# z80test.net
KiCad netlist of a schematic drawn in EAGLE
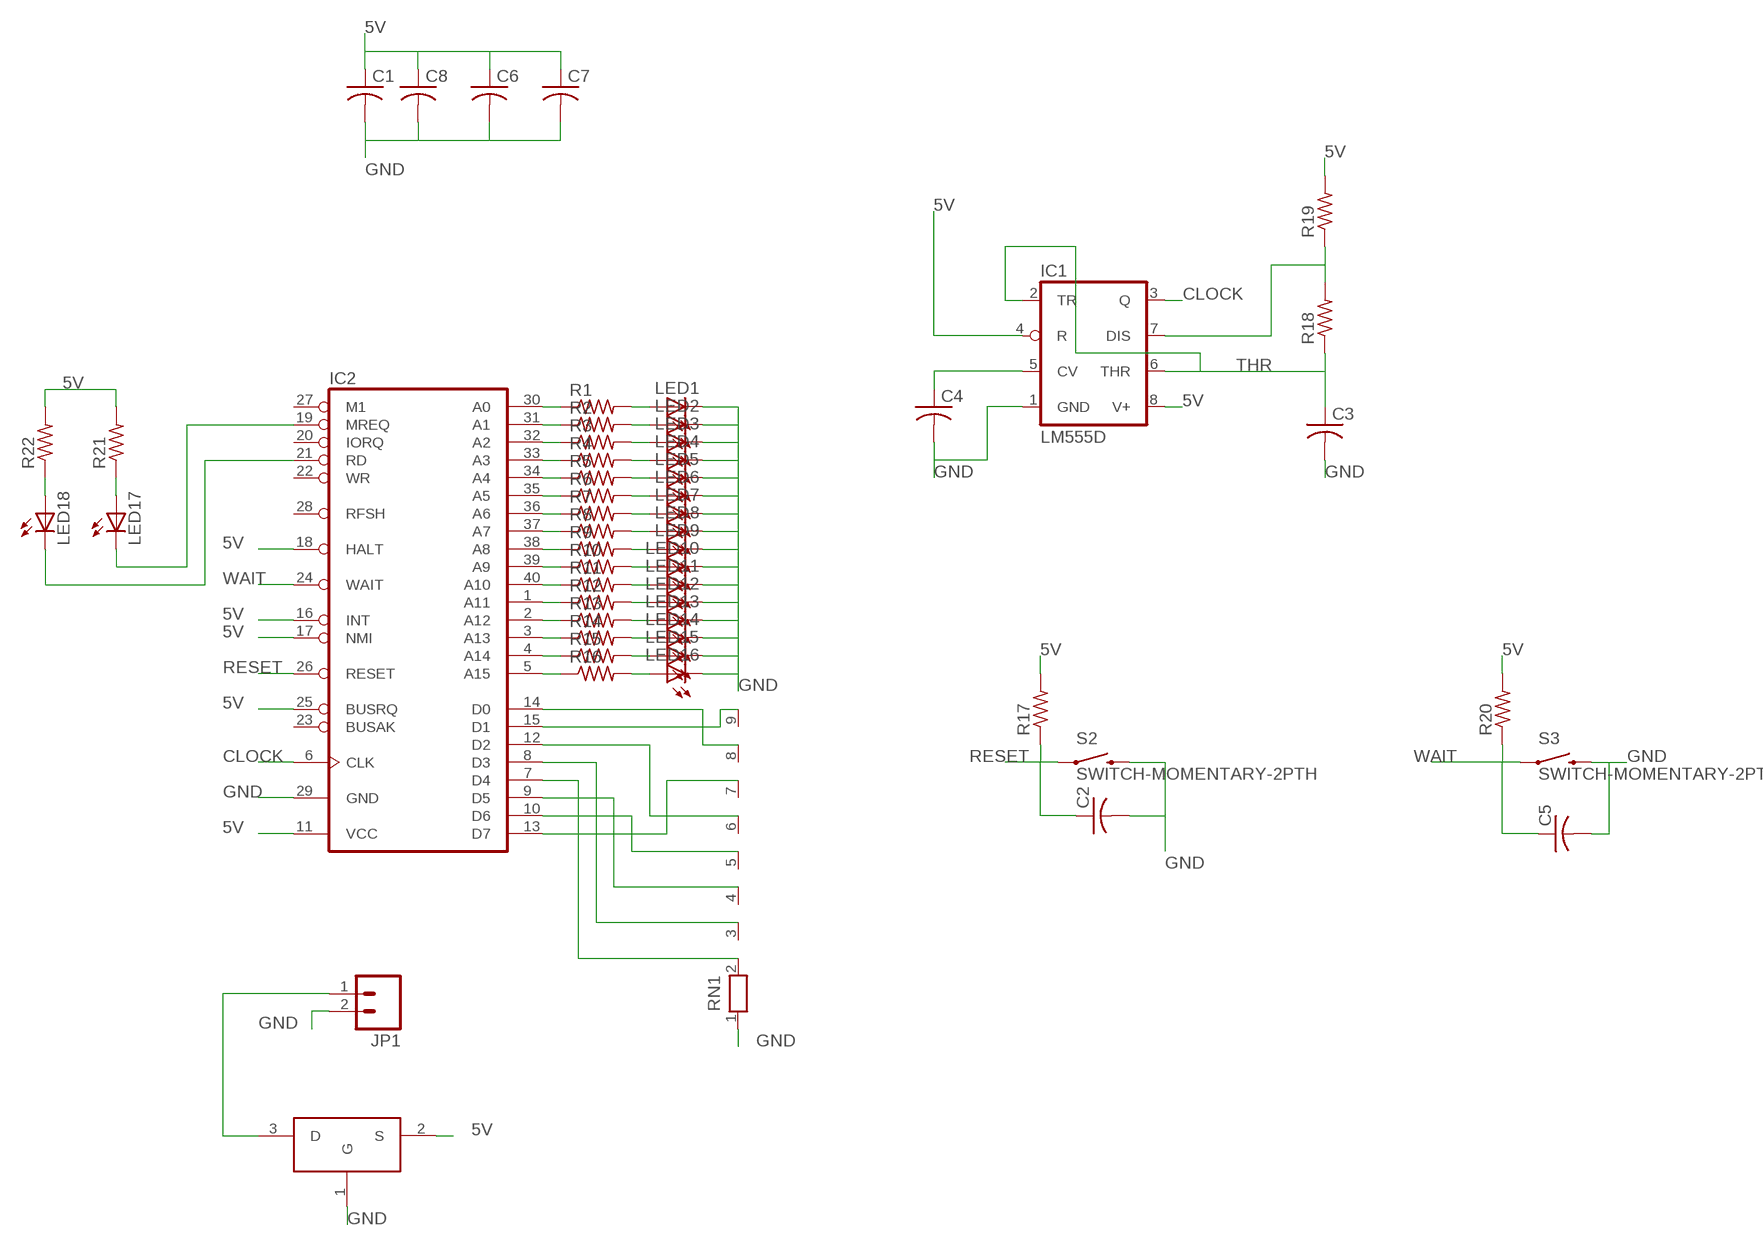
[diagram p0: schematic, sheet 1]

(export (version "E")
  (design (tool "Eeschema 10.0.6"))
  (components
    (comp (ref "C1")
      (value "C-USC0805K")
      (footprint "eagle-import:C0805K")
      (libsource (lib "eagle-import") (part "C-USC0805K"))
    )
    (comp (ref "C2")
      (value "C-USC0603")
      (footprint "eagle-import:C0603")
      (libsource (lib "eagle-import") (part "C-USC0603"))
    )
    (comp (ref "C3")
      (value "C-USC0603")
      (footprint "eagle-import:C0603")
      (libsource (lib "eagle-import") (part "C-USC0603"))
    )
    (comp (ref "C4")
      (value "C-USC0603")
      (footprint "eagle-import:C0603")
      (libsource (lib "eagle-import") (part "C-USC0603"))
    )
    (comp (ref "C5")
      (value "C-USC0603")
      (footprint "eagle-import:C0603")
      (libsource (lib "eagle-import") (part "C-USC0603"))
    )
    (comp (ref "C6")
      (value "C-USC0603")
      (footprint "eagle-import:C0603")
      (libsource (lib "eagle-import") (part "C-USC0603"))
    )
    (comp (ref "C7")
      (value "C-USC0603")
      (footprint "eagle-import:C0603")
      (libsource (lib "eagle-import") (part "C-USC0603"))
    )
    (comp (ref "C8")
      (value "C-USC0603")
      (footprint "eagle-import:C0603")
      (libsource (lib "eagle-import") (part "C-USC0603"))
    )
    (comp (ref "IC1")
      (value "LM555D")
      (footprint "eagle-import:SO08")
      (libsource (lib "eagle-import") (part "555DLM"))
    )
    (comp (ref "IC2")
      (value "Z80CPU")
      (footprint "eagle-import:DIL40")
      (libsource (lib "eagle-import") (part "Z80CPU"))
    )
    (comp (ref "JP1")
      (value "M02PTH")
      (footprint "eagle-import:1X02")
      (libsource (lib "eagle-import") (part "M02PTH"))
    )
    (comp (ref "LED1")
      (value "LEDCHIPLED_0805")
      (footprint "eagle-import:CHIPLED_0805")
      (libsource (lib "eagle-import") (part "LEDCHIPLED_0805"))
    )
    (comp (ref "LED2")
      (value "LEDCHIPLED_0805")
      (footprint "eagle-import:CHIPLED_0805")
      (libsource (lib "eagle-import") (part "LEDCHIPLED_0805"))
    )
    (comp (ref "LED3")
      (value "LEDCHIPLED_0805")
      (footprint "eagle-import:CHIPLED_0805")
      (libsource (lib "eagle-import") (part "LEDCHIPLED_0805"))
    )
    (comp (ref "LED4")
      (value "LEDCHIPLED_0805")
      (footprint "eagle-import:CHIPLED_0805")
      (libsource (lib "eagle-import") (part "LEDCHIPLED_0805"))
    )
    (comp (ref "LED5")
      (value "LEDCHIPLED_0805")
      (footprint "eagle-import:CHIPLED_0805")
      (libsource (lib "eagle-import") (part "LEDCHIPLED_0805"))
    )
    (comp (ref "LED6")
      (value "LEDCHIPLED_0805")
      (footprint "eagle-import:CHIPLED_0805")
      (libsource (lib "eagle-import") (part "LEDCHIPLED_0805"))
    )
    (comp (ref "LED7")
      (value "LEDCHIPLED_0805")
      (footprint "eagle-import:CHIPLED_0805")
      (libsource (lib "eagle-import") (part "LEDCHIPLED_0805"))
    )
    (comp (ref "LED8")
      (value "LEDCHIPLED_0805")
      (footprint "eagle-import:CHIPLED_0805")
      (libsource (lib "eagle-import") (part "LEDCHIPLED_0805"))
    )
    (comp (ref "LED9")
      (value "LEDCHIPLED_0805")
      (footprint "eagle-import:CHIPLED_0805")
      (libsource (lib "eagle-import") (part "LEDCHIPLED_0805"))
    )
    (comp (ref "LED10")
      (value "LEDCHIPLED_0805")
      (footprint "eagle-import:CHIPLED_0805")
      (libsource (lib "eagle-import") (part "LEDCHIPLED_0805"))
    )
    (comp (ref "LED11")
      (value "LEDCHIPLED_0805")
      (footprint "eagle-import:CHIPLED_0805")
      (libsource (lib "eagle-import") (part "LEDCHIPLED_0805"))
    )
    (comp (ref "LED12")
      (value "LEDCHIPLED_0805")
      (footprint "eagle-import:CHIPLED_0805")
      (libsource (lib "eagle-import") (part "LEDCHIPLED_0805"))
    )
    (comp (ref "LED13")
      (value "LEDCHIPLED_0805")
      (footprint "eagle-import:CHIPLED_0805")
      (libsource (lib "eagle-import") (part "LEDCHIPLED_0805"))
    )
    (comp (ref "LED14")
      (value "LEDCHIPLED_0805")
      (footprint "eagle-import:CHIPLED_0805")
      (libsource (lib "eagle-import") (part "LEDCHIPLED_0805"))
    )
    (comp (ref "LED15")
      (value "LEDCHIPLED_0805")
      (footprint "eagle-import:CHIPLED_0805")
      (libsource (lib "eagle-import") (part "LEDCHIPLED_0805"))
    )
    (comp (ref "LED16")
      (value "LEDCHIPLED_0805")
      (footprint "eagle-import:CHIPLED_0805")
      (libsource (lib "eagle-import") (part "LEDCHIPLED_0805"))
    )
    (comp (ref "LED17")
      (value "LEDCHIPLED_0805")
      (footprint "eagle-import:CHIPLED_0805")
      (libsource (lib "eagle-import") (part "LEDCHIPLED_0805"))
    )
    (comp (ref "LED18")
      (value "LEDCHIPLED_0805")
      (footprint "eagle-import:CHIPLED_0805")
      (libsource (lib "eagle-import") (part "LEDCHIPLED_0805"))
    )
    (comp (ref "R1")
      (value "R-US_R0603")
      (footprint "eagle-import:R0603")
      (libsource (lib "eagle-import") (part "R-US_R0603"))
    )
    (comp (ref "R2")
      (value "R-US_R0603")
      (footprint "eagle-import:R0603")
      (libsource (lib "eagle-import") (part "R-US_R0603"))
    )
    (comp (ref "R3")
      (value "R-US_R0603")
      (footprint "eagle-import:R0603")
      (libsource (lib "eagle-import") (part "R-US_R0603"))
    )
    (comp (ref "R4")
      (value "R-US_R0603")
      (footprint "eagle-import:R0603")
      (libsource (lib "eagle-import") (part "R-US_R0603"))
    )
    (comp (ref "R5")
      (value "R-US_R0603")
      (footprint "eagle-import:R0603")
      (libsource (lib "eagle-import") (part "R-US_R0603"))
    )
    (comp (ref "R6")
      (value "R-US_R0603")
      (footprint "eagle-import:R0603")
      (libsource (lib "eagle-import") (part "R-US_R0603"))
    )
    (comp (ref "R7")
      (value "R-US_R0603")
      (footprint "eagle-import:R0603")
      (libsource (lib "eagle-import") (part "R-US_R0603"))
    )
    (comp (ref "R8")
      (value "R-US_R0603")
      (footprint "eagle-import:R0603")
      (libsource (lib "eagle-import") (part "R-US_R0603"))
    )
    (comp (ref "R9")
      (value "R-US_R0603")
      (footprint "eagle-import:R0603")
      (libsource (lib "eagle-import") (part "R-US_R0603"))
    )
    (comp (ref "R10")
      (value "R-US_R0603")
      (footprint "eagle-import:R0603")
      (libsource (lib "eagle-import") (part "R-US_R0603"))
    )
    (comp (ref "R11")
      (value "R-US_R0603")
      (footprint "eagle-import:R0603")
      (libsource (lib "eagle-import") (part "R-US_R0603"))
    )
    (comp (ref "R12")
      (value "R-US_R0603")
      (footprint "eagle-import:R0603")
      (libsource (lib "eagle-import") (part "R-US_R0603"))
    )
    (comp (ref "R13")
      (value "R-US_R0603")
      (footprint "eagle-import:R0603")
      (libsource (lib "eagle-import") (part "R-US_R0603"))
    )
    (comp (ref "R14")
      (value "R-US_R0603")
      (footprint "eagle-import:R0603")
      (libsource (lib "eagle-import") (part "R-US_R0603"))
    )
    (comp (ref "R15")
      (value "R-US_R0603")
      (footprint "eagle-import:R0603")
      (libsource (lib "eagle-import") (part "R-US_R0603"))
    )
    (comp (ref "R16")
      (value "R-US_R0603")
      (footprint "eagle-import:R0603")
      (libsource (lib "eagle-import") (part "R-US_R0603"))
    )
    (comp (ref "R17")
      (value "R-US_R0603")
      (footprint "eagle-import:R0603")
      (libsource (lib "eagle-import") (part "R-US_R0603"))
    )
    (comp (ref "R18")
      (value "R-US_R0603")
      (footprint "eagle-import:R0603")
      (libsource (lib "eagle-import") (part "R-US_R0603"))
    )
    (comp (ref "R19")
      (value "R-US_R0603")
      (footprint "eagle-import:R0603")
      (libsource (lib "eagle-import") (part "R-US_R0603"))
    )
    (comp (ref "R20")
      (value "R-US_R0603")
      (footprint "eagle-import:R0603")
      (libsource (lib "eagle-import") (part "R-US_R0603"))
    )
    (comp (ref "R21")
      (value "R-US_R0603")
      (footprint "eagle-import:R0603")
      (libsource (lib "eagle-import") (part "R-US_R0603"))
    )
    (comp (ref "R22")
      (value "R-US_R0603")
      (footprint "eagle-import:R0603")
      (libsource (lib "eagle-import") (part "R-US_R0603"))
    )
    (comp (ref "RN1")
      (value "RN08")
      (footprint "eagle-import:RN-9")
      (libsource (lib "eagle-import") (part "RN08"))
    )
    (comp (ref "S2")
      (value "SWITCH-MOMENTARY-2PTH")
      (footprint "eagle-import:TACTILE-PTH")
      (libsource (lib "eagle-import") (part "SWITCH-MOMENTARY-2PTH"))
    )
    (comp (ref "S3")
      (value "SWITCH-MOMENTARY-2PTH")
      (footprint "eagle-import:TACTILE-PTH")
      (libsource (lib "eagle-import") (part "SWITCH-MOMENTARY-2PTH"))
    )
    (comp (ref "U$1")
      (value "PMOS_RP")
      (footprint "eagle-import:SOT23-3")
      (libsource (lib "eagle-import") (part "PMOS_RP"))
    )
  )
  (nets
    (net (code "1") (name "/5V") (class "Default")
      (node (ref "C1") (pin "1") (pinfunction "1_1") (pintype "passive"))
      (node (ref "C6") (pin "1") (pinfunction "1_1") (pintype "passive"))
      (node (ref "C7") (pin "1") (pinfunction "1_1") (pintype "passive"))
      (node (ref "C8") (pin "1") (pinfunction "1_1") (pintype "passive"))
      (node (ref "IC1") (pin "4") (pinfunction "R_4") (pintype "input"))
      (node (ref "IC1") (pin "8") (pinfunction "V+_8") (pintype "power_in"))
      (node (ref "IC2") (pin "11") (pinfunction "VCC_11") (pintype "power_in"))
      (node (ref "IC2") (pin "16") (pinfunction "INT_16") (pintype "input"))
      (node (ref "IC2") (pin "17") (pinfunction "NMI_17") (pintype "input"))
      (node (ref "IC2") (pin "18") (pinfunction "HALT_18") (pintype "output"))
      (node (ref "IC2") (pin "25") (pinfunction "BUSRQ_25") (pintype "input"))
      (node (ref "R17") (pin "2") (pinfunction "2_2") (pintype "passive"))
      (node (ref "R19") (pin "2") (pinfunction "2_2") (pintype "passive"))
      (node (ref "R20") (pin "2") (pinfunction "2_2") (pintype "passive"))
      (node (ref "R21") (pin "2") (pinfunction "2_2") (pintype "passive"))
      (node (ref "R22") (pin "2") (pinfunction "2_2") (pintype "passive"))
      (node (ref "U$1") (pin "2") (pinfunction "S_2") (pintype "bidirectional"))
    )
    (net (code "2") (name "/CLOCK") (class "Default")
      (node (ref "IC1") (pin "3") (pinfunction "Q_3") (pintype "output"))
      (node (ref "IC2") (pin "6") (pinfunction "CLK_6") (pintype "input"))
    )
    (net (code "3") (name "/GND") (class "Default")
      (node (ref "C1") (pin "2") (pinfunction "2_2") (pintype "passive"))
      (node (ref "C2") (pin "2") (pinfunction "2_2") (pintype "passive"))
      (node (ref "C3") (pin "2") (pinfunction "2_2") (pintype "passive"))
      (node (ref "C4") (pin "2") (pinfunction "2_2") (pintype "passive"))
      (node (ref "C5") (pin "2") (pinfunction "2_2") (pintype "passive"))
      (node (ref "C6") (pin "2") (pinfunction "2_2") (pintype "passive"))
      (node (ref "C7") (pin "2") (pinfunction "2_2") (pintype "passive"))
      (node (ref "C8") (pin "2") (pinfunction "2_2") (pintype "passive"))
      (node (ref "IC1") (pin "1") (pinfunction "GND_1") (pintype "power_in"))
      (node (ref "IC2") (pin "29") (pinfunction "GND_29") (pintype "power_in"))
      (node (ref "JP1") (pin "2") (pinfunction "2_2") (pintype "passive"))
      (node (ref "LED1") (pin "C") (pinfunction "C_C") (pintype "passive"))
      (node (ref "LED10") (pin "C") (pinfunction "C_C") (pintype "passive"))
      (node (ref "LED11") (pin "C") (pinfunction "C_C") (pintype "passive"))
      (node (ref "LED12") (pin "C") (pinfunction "C_C") (pintype "passive"))
      (node (ref "LED13") (pin "C") (pinfunction "C_C") (pintype "passive"))
      (node (ref "LED14") (pin "C") (pinfunction "C_C") (pintype "passive"))
      (node (ref "LED15") (pin "C") (pinfunction "C_C") (pintype "passive"))
      (node (ref "LED16") (pin "C") (pinfunction "C_C") (pintype "passive"))
      (node (ref "LED2") (pin "C") (pinfunction "C_C") (pintype "passive"))
      (node (ref "LED3") (pin "C") (pinfunction "C_C") (pintype "passive"))
      (node (ref "LED4") (pin "C") (pinfunction "C_C") (pintype "passive"))
      (node (ref "LED5") (pin "C") (pinfunction "C_C") (pintype "passive"))
      (node (ref "LED6") (pin "C") (pinfunction "C_C") (pintype "passive"))
      (node (ref "LED7") (pin "C") (pinfunction "C_C") (pintype "passive"))
      (node (ref "LED8") (pin "C") (pinfunction "C_C") (pintype "passive"))
      (node (ref "LED9") (pin "C") (pinfunction "C_C") (pintype "passive"))
      (node (ref "RN1") (pin "1") (pinfunction "1_1") (pintype "passive"))
      (node (ref "S2") (pin "3") (pinfunction "2_3") (pintype "passive"))
      (node (ref "S3") (pin "3") (pinfunction "2_3") (pintype "passive"))
      (node (ref "U$1") (pin "1") (pinfunction "G_1") (pintype "bidirectional"))
    )
    (net (code "4") (name "/RESET") (class "Default")
      (node (ref "C2") (pin "1") (pinfunction "1_1") (pintype "passive"))
      (node (ref "IC2") (pin "26") (pinfunction "RESET_26") (pintype "input"))
      (node (ref "R17") (pin "1") (pinfunction "1_1") (pintype "passive"))
      (node (ref "S2") (pin "1") (pinfunction "1_1") (pintype "passive"))
    )
    (net (code "5") (name "/THR") (class "Default")
      (node (ref "C3") (pin "1") (pinfunction "1_1") (pintype "passive"))
      (node (ref "IC1") (pin "2") (pinfunction "TR_2") (pintype "input"))
      (node (ref "IC1") (pin "6") (pinfunction "THR_6") (pintype "input"))
      (node (ref "R18") (pin "1") (pinfunction "1_1") (pintype "passive"))
    )
    (net (code "6") (name "/WAIT") (class "Default")
      (node (ref "C5") (pin "1") (pinfunction "1_1") (pintype "passive"))
      (node (ref "IC2") (pin "24") (pinfunction "WAIT_24") (pintype "input"))
      (node (ref "R20") (pin "1") (pinfunction "1_1") (pintype "passive"))
      (node (ref "S3") (pin "1") (pinfunction "1_1") (pintype "passive"))
    )
    (net (code "7") (name "Net-(IC1-CV)") (class "Default")
      (node (ref "C4") (pin "1") (pinfunction "1_1") (pintype "passive"))
      (node (ref "IC1") (pin "5") (pinfunction "CV_5") (pintype "input"))
    )
    (net (code "8") (name "Net-(IC1-DIS)") (class "Default")
      (node (ref "IC1") (pin "7") (pinfunction "DIS_7") (pintype "input"))
      (node (ref "R18") (pin "2") (pinfunction "2_2") (pintype "passive"))
      (node (ref "R19") (pin "1") (pinfunction "1_1") (pintype "passive"))
    )
    (net (code "9") (name "Net-(IC2-A0)") (class "Default")
      (node (ref "IC2") (pin "30") (pinfunction "A0_30") (pintype "output"))
      (node (ref "R1") (pin "1") (pinfunction "1_1") (pintype "passive"))
    )
    (net (code "10") (name "Net-(IC2-A1)") (class "Default")
      (node (ref "IC2") (pin "31") (pinfunction "A1_31") (pintype "output"))
      (node (ref "R2") (pin "1") (pinfunction "1_1") (pintype "passive"))
    )
    (net (code "11") (name "Net-(IC2-A2)") (class "Default")
      (node (ref "IC2") (pin "32") (pinfunction "A2_32") (pintype "output"))
      (node (ref "R3") (pin "1") (pinfunction "1_1") (pintype "passive"))
    )
    (net (code "12") (name "Net-(IC2-A3)") (class "Default")
      (node (ref "IC2") (pin "33") (pinfunction "A3_33") (pintype "output"))
      (node (ref "R4") (pin "1") (pinfunction "1_1") (pintype "passive"))
    )
    (net (code "13") (name "Net-(IC2-A4)") (class "Default")
      (node (ref "IC2") (pin "34") (pinfunction "A4_34") (pintype "output"))
      (node (ref "R5") (pin "1") (pinfunction "1_1") (pintype "passive"))
    )
    (net (code "14") (name "Net-(IC2-A5)") (class "Default")
      (node (ref "IC2") (pin "35") (pinfunction "A5_35") (pintype "output"))
      (node (ref "R6") (pin "1") (pinfunction "1_1") (pintype "passive"))
    )
    (net (code "15") (name "Net-(IC2-A6)") (class "Default")
      (node (ref "IC2") (pin "36") (pinfunction "A6_36") (pintype "output"))
      (node (ref "R7") (pin "1") (pinfunction "1_1") (pintype "passive"))
    )
    (net (code "16") (name "Net-(IC2-A7)") (class "Default")
      (node (ref "IC2") (pin "37") (pinfunction "A7_37") (pintype "output"))
      (node (ref "R8") (pin "1") (pinfunction "1_1") (pintype "passive"))
    )
    (net (code "17") (name "Net-(IC2-A8)") (class "Default")
      (node (ref "IC2") (pin "38") (pinfunction "A8_38") (pintype "output"))
      (node (ref "R9") (pin "1") (pinfunction "1_1") (pintype "passive"))
    )
    (net (code "18") (name "Net-(IC2-A9)") (class "Default")
      (node (ref "IC2") (pin "39") (pinfunction "A9_39") (pintype "output"))
      (node (ref "R10") (pin "1") (pinfunction "1_1") (pintype "passive"))
    )
    (net (code "19") (name "Net-(IC2-A10)") (class "Default")
      (node (ref "IC2") (pin "40") (pinfunction "A10_40") (pintype "output"))
      (node (ref "R11") (pin "1") (pinfunction "1_1") (pintype "passive"))
    )
    (net (code "20") (name "Net-(IC2-A11)") (class "Default")
      (node (ref "IC2") (pin "1") (pinfunction "A11_1") (pintype "output"))
      (node (ref "R12") (pin "1") (pinfunction "1_1") (pintype "passive"))
    )
    (net (code "21") (name "Net-(IC2-A12)") (class "Default")
      (node (ref "IC2") (pin "2") (pinfunction "A12_2") (pintype "output"))
      (node (ref "R13") (pin "1") (pinfunction "1_1") (pintype "passive"))
    )
    (net (code "22") (name "Net-(IC2-A13)") (class "Default")
      (node (ref "IC2") (pin "3") (pinfunction "A13_3") (pintype "output"))
      (node (ref "R14") (pin "1") (pinfunction "1_1") (pintype "passive"))
    )
    (net (code "23") (name "Net-(IC2-A14)") (class "Default")
      (node (ref "IC2") (pin "4") (pinfunction "A14_4") (pintype "output"))
      (node (ref "R15") (pin "1") (pinfunction "1_1") (pintype "passive"))
    )
    (net (code "24") (name "Net-(IC2-A15)") (class "Default")
      (node (ref "IC2") (pin "5") (pinfunction "A15_5") (pintype "output"))
      (node (ref "R16") (pin "1") (pinfunction "1_1") (pintype "passive"))
    )
    (net (code "25") (name "Net-(IC2-D0)") (class "Default")
      (node (ref "IC2") (pin "14") (pinfunction "D0_14") (pintype "bidirectional"))
      (node (ref "RN1") (pin "8") (pinfunction "8_8") (pintype "passive"))
    )
    (net (code "26") (name "Net-(IC2-D1)") (class "Default")
      (node (ref "IC2") (pin "15") (pinfunction "D1_15") (pintype "bidirectional"))
      (node (ref "RN1") (pin "9") (pinfunction "9_9") (pintype "passive"))
    )
    (net (code "27") (name "Net-(IC2-D2)") (class "Default")
      (node (ref "IC2") (pin "12") (pinfunction "D2_12") (pintype "bidirectional"))
      (node (ref "RN1") (pin "6") (pinfunction "6_6") (pintype "passive"))
    )
    (net (code "28") (name "Net-(IC2-D3)") (class "Default")
      (node (ref "IC2") (pin "8") (pinfunction "D3_8") (pintype "bidirectional"))
      (node (ref "RN1") (pin "3") (pinfunction "3_3") (pintype "passive"))
    )
    (net (code "29") (name "Net-(IC2-D4)") (class "Default")
      (node (ref "IC2") (pin "7") (pinfunction "D4_7") (pintype "bidirectional"))
      (node (ref "RN1") (pin "2") (pinfunction "2_2") (pintype "passive"))
    )
    (net (code "30") (name "Net-(IC2-D5)") (class "Default")
      (node (ref "IC2") (pin "9") (pinfunction "D5_9") (pintype "bidirectional"))
      (node (ref "RN1") (pin "4") (pinfunction "4_4") (pintype "passive"))
    )
    (net (code "31") (name "Net-(IC2-D6)") (class "Default")
      (node (ref "IC2") (pin "10") (pinfunction "D6_10") (pintype "bidirectional"))
      (node (ref "RN1") (pin "5") (pinfunction "5_5") (pintype "passive"))
    )
    (net (code "32") (name "Net-(IC2-D7)") (class "Default")
      (node (ref "IC2") (pin "13") (pinfunction "D7_13") (pintype "bidirectional"))
      (node (ref "RN1") (pin "7") (pinfunction "7_7") (pintype "passive"))
    )
    (net (code "33") (name "Net-(IC2-MREQ)") (class "Default")
      (node (ref "IC2") (pin "19") (pinfunction "MREQ_19") (pintype "output"))
      (node (ref "LED17") (pin "C") (pinfunction "C_C") (pintype "passive"))
    )
    (net (code "34") (name "Net-(IC2-RD)") (class "Default")
      (node (ref "IC2") (pin "21") (pinfunction "RD_21") (pintype "output"))
      (node (ref "LED18") (pin "C") (pinfunction "C_C") (pintype "passive"))
    )
    (net (code "35") (name "Net-(LED1-PadA)") (class "Default")
      (node (ref "LED1") (pin "A") (pinfunction "A_A") (pintype "passive"))
      (node (ref "R1") (pin "2") (pinfunction "2_2") (pintype "passive"))
    )
    (net (code "36") (name "Net-(LED2-PadA)") (class "Default")
      (node (ref "LED2") (pin "A") (pinfunction "A_A") (pintype "passive"))
      (node (ref "R2") (pin "2") (pinfunction "2_2") (pintype "passive"))
    )
    (net (code "37") (name "Net-(LED3-PadA)") (class "Default")
      (node (ref "LED3") (pin "A") (pinfunction "A_A") (pintype "passive"))
      (node (ref "R3") (pin "2") (pinfunction "2_2") (pintype "passive"))
    )
    (net (code "38") (name "Net-(LED4-PadA)") (class "Default")
      (node (ref "LED4") (pin "A") (pinfunction "A_A") (pintype "passive"))
      (node (ref "R4") (pin "2") (pinfunction "2_2") (pintype "passive"))
    )
    (net (code "39") (name "Net-(LED5-PadA)") (class "Default")
      (node (ref "LED5") (pin "A") (pinfunction "A_A") (pintype "passive"))
      (node (ref "R5") (pin "2") (pinfunction "2_2") (pintype "passive"))
    )
    (net (code "40") (name "Net-(LED6-PadA)") (class "Default")
      (node (ref "LED6") (pin "A") (pinfunction "A_A") (pintype "passive"))
      (node (ref "R6") (pin "2") (pinfunction "2_2") (pintype "passive"))
    )
    (net (code "41") (name "Net-(LED7-PadA)") (class "Default")
      (node (ref "LED7") (pin "A") (pinfunction "A_A") (pintype "passive"))
      (node (ref "R7") (pin "2") (pinfunction "2_2") (pintype "passive"))
    )
    (net (code "42") (name "Net-(LED8-PadA)") (class "Default")
      (node (ref "LED8") (pin "A") (pinfunction "A_A") (pintype "passive"))
      (node (ref "R8") (pin "2") (pinfunction "2_2") (pintype "passive"))
    )
    (net (code "43") (name "Net-(LED9-PadA)") (class "Default")
      (node (ref "LED9") (pin "A") (pinfunction "A_A") (pintype "passive"))
      (node (ref "R9") (pin "2") (pinfunction "2_2") (pintype "passive"))
    )
    (net (code "44") (name "Net-(LED10-PadA)") (class "Default")
      (node (ref "LED10") (pin "A") (pinfunction "A_A") (pintype "passive"))
      (node (ref "R10") (pin "2") (pinfunction "2_2") (pintype "passive"))
    )
    (net (code "45") (name "Net-(LED11-PadA)") (class "Default")
      (node (ref "LED11") (pin "A") (pinfunction "A_A") (pintype "passive"))
      (node (ref "R11") (pin "2") (pinfunction "2_2") (pintype "passive"))
    )
    (net (code "46") (name "Net-(LED12-PadA)") (class "Default")
      (node (ref "LED12") (pin "A") (pinfunction "A_A") (pintype "passive"))
      (node (ref "R12") (pin "2") (pinfunction "2_2") (pintype "passive"))
    )
    (net (code "47") (name "Net-(LED13-PadA)") (class "Default")
      (node (ref "LED13") (pin "A") (pinfunction "A_A") (pintype "passive"))
      (node (ref "R13") (pin "2") (pinfunction "2_2") (pintype "passive"))
    )
    (net (code "48") (name "Net-(LED14-PadA)") (class "Default")
      (node (ref "LED14") (pin "A") (pinfunction "A_A") (pintype "passive"))
      (node (ref "R14") (pin "2") (pinfunction "2_2") (pintype "passive"))
    )
    (net (code "49") (name "Net-(LED15-PadA)") (class "Default")
      (node (ref "LED15") (pin "A") (pinfunction "A_A") (pintype "passive"))
      (node (ref "R15") (pin "2") (pinfunction "2_2") (pintype "passive"))
    )
    (net (code "50") (name "Net-(LED16-PadA)") (class "Default")
      (node (ref "LED16") (pin "A") (pinfunction "A_A") (pintype "passive"))
      (node (ref "R16") (pin "2") (pinfunction "2_2") (pintype "passive"))
    )
    (net (code "51") (name "Net-(LED17-PadA)") (class "Default")
      (node (ref "LED17") (pin "A") (pinfunction "A_A") (pintype "passive"))
      (node (ref "R21") (pin "1") (pinfunction "1_1") (pintype "passive"))
    )
    (net (code "52") (name "Net-(LED18-PadA)") (class "Default")
      (node (ref "LED18") (pin "A") (pinfunction "A_A") (pintype "passive"))
      (node (ref "R22") (pin "1") (pinfunction "1_1") (pintype "passive"))
    )
    (net (code "53") (name "Net-(U$1-D)") (class "Default")
      (node (ref "JP1") (pin "1") (pinfunction "1_1") (pintype "passive"))
      (node (ref "U$1") (pin "3") (pinfunction "D_3") (pintype "bidirectional"))
    )
    (net (code "54") (name "unconnected-(IC2-BUSAK-Pad23)") (class "Default")
      (node (ref "IC2") (pin "23") (pinfunction "BUSAK_23") (pintype "output"))
    )
    (net (code "55") (name "unconnected-(IC2-IORQ-Pad20)") (class "Default")
      (node (ref "IC2") (pin "20") (pinfunction "IORQ_20") (pintype "output"))
    )
    (net (code "56") (name "unconnected-(IC2-M1-Pad27)") (class "Default")
      (node (ref "IC2") (pin "27") (pinfunction "M1_27") (pintype "output"))
    )
    (net (code "57") (name "unconnected-(IC2-RFSH-Pad28)") (class "Default")
      (node (ref "IC2") (pin "28") (pinfunction "RFSH_28") (pintype "output"))
    )
    (net (code "58") (name "unconnected-(IC2-WR-Pad22)") (class "Default")
      (node (ref "IC2") (pin "22") (pinfunction "WR_22") (pintype "output"))
    )
  )
)
